# punch_driver_Rev_A.net
KiCad netlist of a schematic drawn in EAGLE
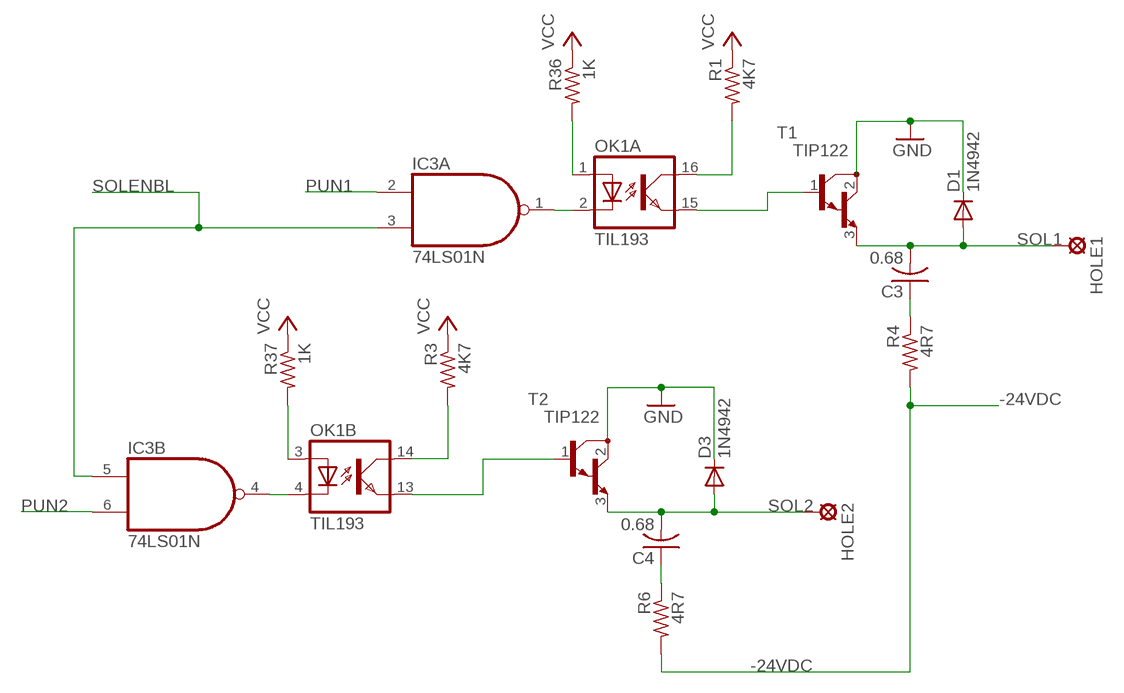
[diagram p0: schematic, sheet 1]
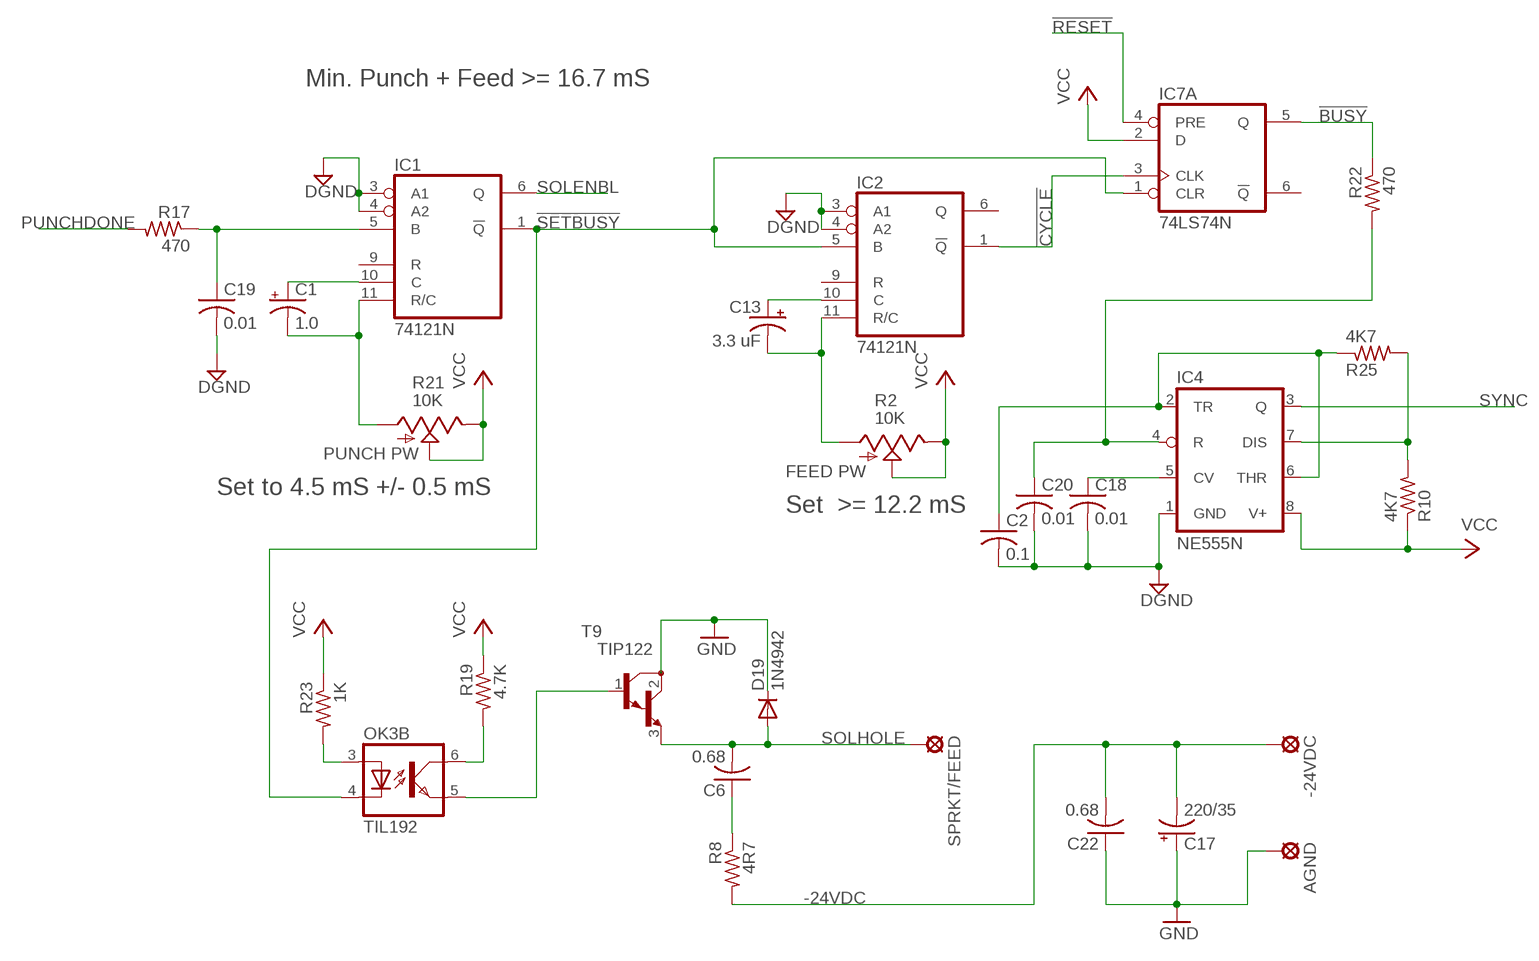
[diagram p1: schematic, sheet 2]
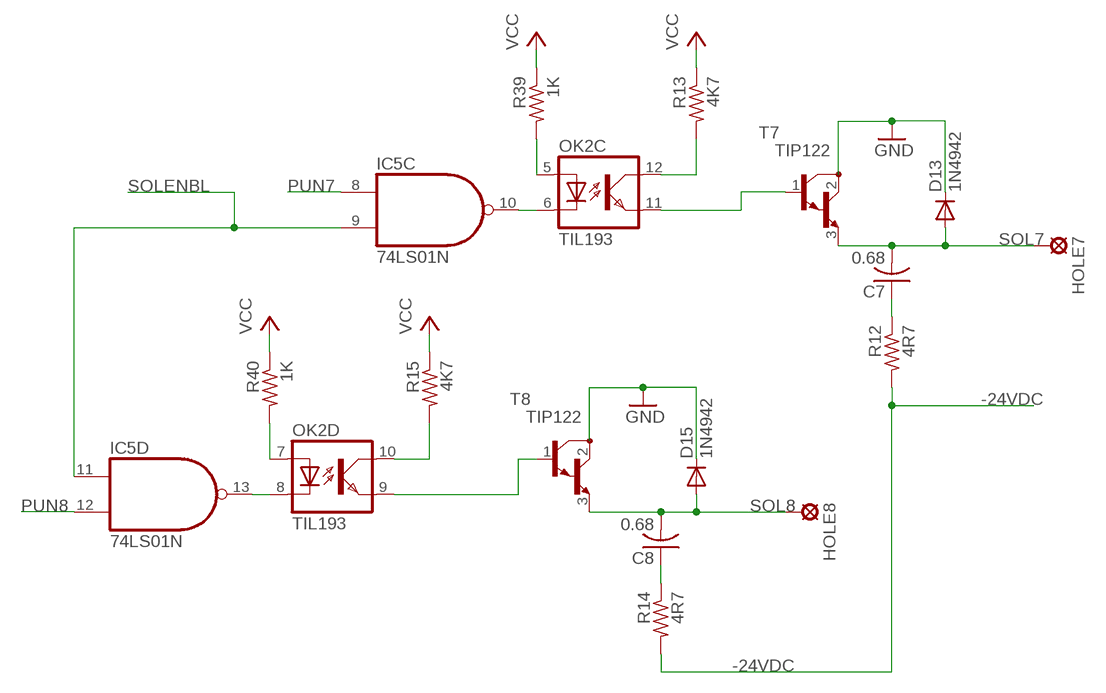
[diagram p2: schematic, sheet 3]
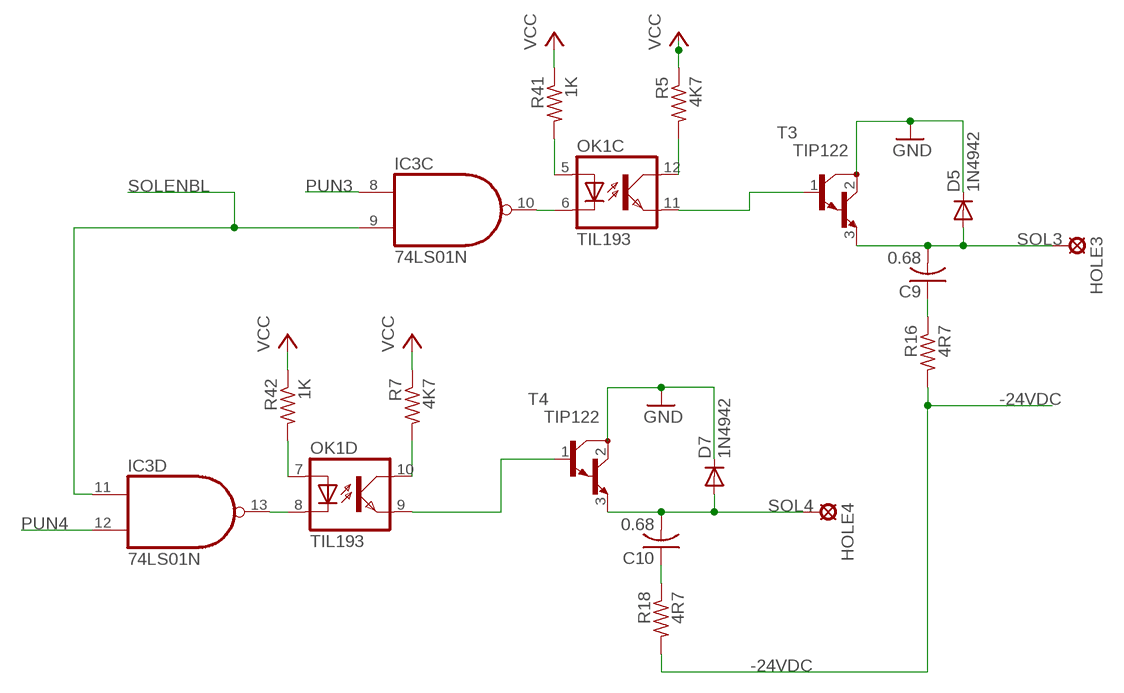
[diagram p3: schematic, sheet 4]
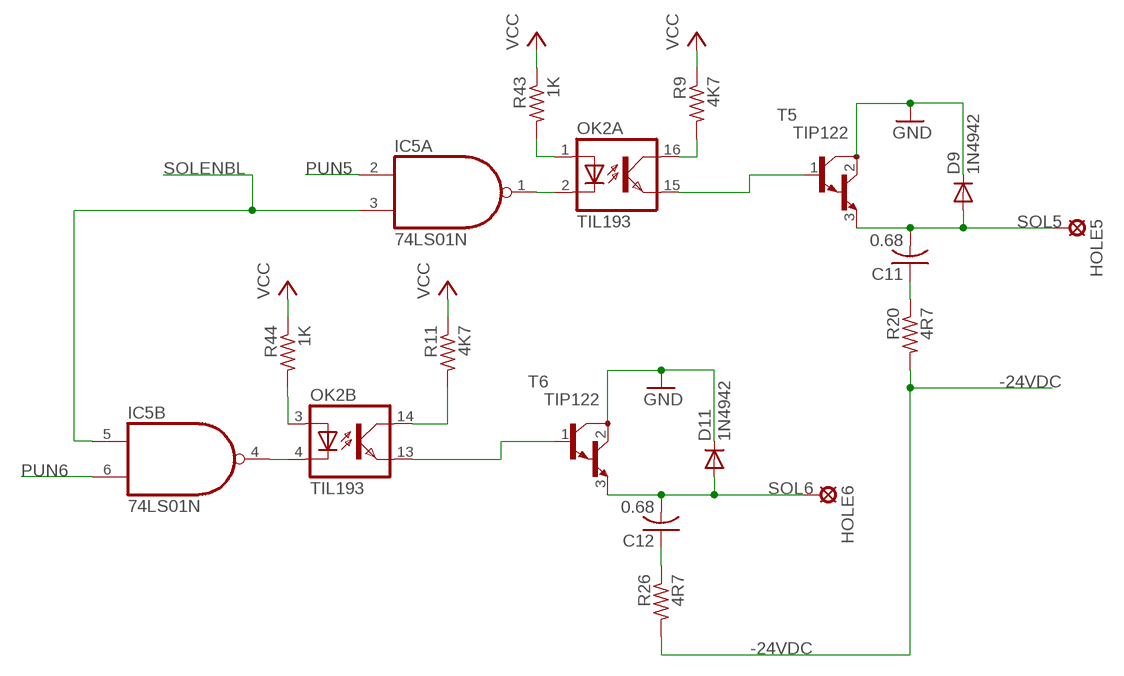
[diagram p4: schematic, sheet 5]
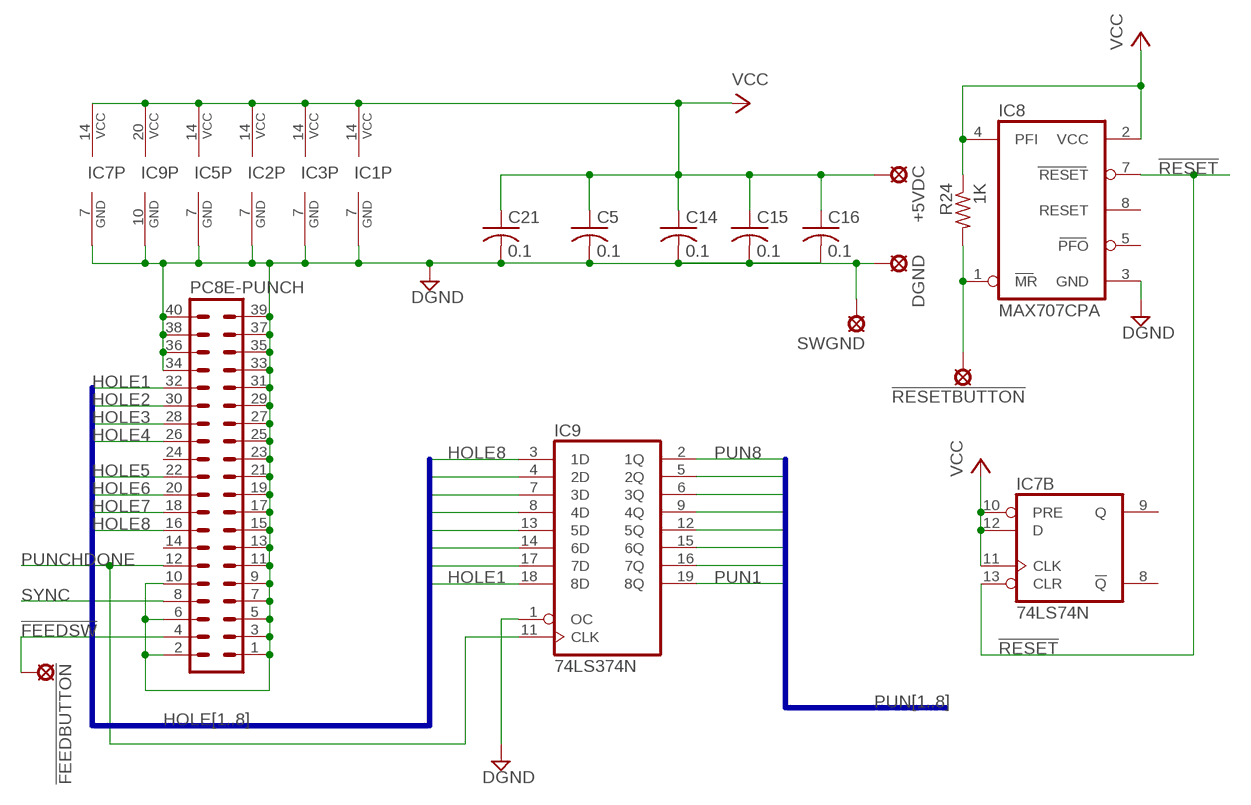
[diagram p5: schematic, sheet 6]

(export (version "E")
  (design (tool "Eeschema 10.0.6"))
  (components
    (comp (ref "C3")
      (value "0.68")
      (footprint "eagle-import:C075-042X103")
      (libsource (lib "eagle-import") (part "C-US075-042X103"))
    )
    (comp (ref "C4")
      (value "0.68")
      (footprint "eagle-import:C075-042X103")
      (libsource (lib "eagle-import") (part "C-US075-042X103"))
    )
    (comp (ref "D1")
      (value "1N4942")
      (footprint "eagle-import:DO41-10")
      (libsource (lib "eagle-import") (part "1N4942"))
    )
    (comp (ref "D3")
      (value "1N4942")
      (footprint "eagle-import:DO41-10")
      (libsource (lib "eagle-import") (part "1N4942"))
    )
    (comp (ref "HOLE1")
      (value "SE13")
      (footprint "eagle-import:SE13")
      (libsource (lib "eagle-import") (part "SE13"))
    )
    (comp (ref "HOLE2")
      (value "SE13")
      (footprint "eagle-import:SE13")
      (libsource (lib "eagle-import") (part "SE13"))
    )
    (comp (ref "IC3")
      (value "74LS01N")
      (footprint "eagle-import:DIL14")
      (libsource (lib "eagle-import") (part "7401NLS"))
    )
    (comp (ref "OK1")
      (value "TIL193")
      (footprint "eagle-import:DIL16")
      (libsource (lib "eagle-import") (part "TIL193"))
    )
    (comp (ref "R1")
      (value "4K7")
      (footprint "eagle-import:0204_5")
      (libsource (lib "eagle-import") (part "R-US_0204/5"))
    )
    (comp (ref "R3")
      (value "4K7")
      (footprint "eagle-import:0204_5")
      (libsource (lib "eagle-import") (part "R-US_0204/5"))
    )
    (comp (ref "R4")
      (value "4R7")
      (footprint "eagle-import:0207_10")
      (libsource (lib "eagle-import") (part "R-US_0207/10"))
    )
    (comp (ref "R6")
      (value "4R7")
      (footprint "eagle-import:0207_10")
      (libsource (lib "eagle-import") (part "R-US_0207/10"))
    )
    (comp (ref "R36")
      (value "1K")
      (footprint "eagle-import:0204_5")
      (libsource (lib "eagle-import") (part "R-US_0204/5"))
    )
    (comp (ref "R37")
      (value "1K")
      (footprint "eagle-import:0204_5")
      (libsource (lib "eagle-import") (part "R-US_0204/5"))
    )
    (comp (ref "T1")
      (value "TIP122")
      (footprint "eagle-import:TO220")
      (libsource (lib "eagle-import") (part "TIP122"))
    )
    (comp (ref "T2")
      (value "TIP122")
      (footprint "eagle-import:TO220")
      (libsource (lib "eagle-import") (part "TIP122"))
    )
    (comp (ref "C7")
      (value "0.68")
      (footprint "eagle-import:C075-042X103")
      (libsource (lib "eagle-import") (part "C-US075-042X103"))
    )
    (comp (ref "C8")
      (value "0.68")
      (footprint "eagle-import:C075-042X103")
      (libsource (lib "eagle-import") (part "C-US075-042X103"))
    )
    (comp (ref "D13")
      (value "1N4942")
      (footprint "eagle-import:DO41-10")
      (libsource (lib "eagle-import") (part "1N4942"))
    )
    (comp (ref "D15")
      (value "1N4942")
      (footprint "eagle-import:DO41-10")
      (libsource (lib "eagle-import") (part "1N4942"))
    )
    (comp (ref "HOLE7")
      (value "SE13")
      (footprint "eagle-import:SE13")
      (libsource (lib "eagle-import") (part "SE13"))
    )
    (comp (ref "HOLE8")
      (value "SE13")
      (footprint "eagle-import:SE13")
      (libsource (lib "eagle-import") (part "SE13"))
    )
    (comp (ref "IC5")
      (value "74LS01N")
      (footprint "eagle-import:DIL14")
      (libsource (lib "eagle-import") (part "7401NLS"))
    )
    (comp (ref "OK2")
      (value "TIL193")
      (footprint "eagle-import:DIL16")
      (libsource (lib "eagle-import") (part "TIL193"))
    )
    (comp (ref "R12")
      (value "4R7")
      (footprint "eagle-import:0207_10")
      (libsource (lib "eagle-import") (part "R-US_0207/10"))
    )
    (comp (ref "R13")
      (value "4K7")
      (footprint "eagle-import:0204_5")
      (libsource (lib "eagle-import") (part "R-US_0204/5"))
    )
    (comp (ref "R14")
      (value "4R7")
      (footprint "eagle-import:0207_10")
      (libsource (lib "eagle-import") (part "R-US_0207/10"))
    )
    (comp (ref "R15")
      (value "4K7")
      (footprint "eagle-import:0204_5")
      (libsource (lib "eagle-import") (part "R-US_0204/5"))
    )
    (comp (ref "R39")
      (value "1K")
      (footprint "eagle-import:0204_5")
      (libsource (lib "eagle-import") (part "R-US_0204/5"))
    )
    (comp (ref "R40")
      (value "1K")
      (footprint "eagle-import:0204_5")
      (libsource (lib "eagle-import") (part "R-US_0204/5"))
    )
    (comp (ref "T7")
      (value "TIP122")
      (footprint "eagle-import:TO220")
      (libsource (lib "eagle-import") (part "TIP122"))
    )
    (comp (ref "T8")
      (value "TIP122")
      (footprint "eagle-import:TO220")
      (libsource (lib "eagle-import") (part "TIP122"))
    )
    (comp (ref "-24VDC")
      (value "SE13")
      (footprint "eagle-import:SE13")
      (libsource (lib "eagle-import") (part "SE13"))
    )
    (comp (ref "AGND")
      (value "SE13")
      (footprint "eagle-import:SE13")
      (libsource (lib "eagle-import") (part "SE13"))
    )
    (comp (ref "C1")
      (value "1.0")
      (footprint "eagle-import:E5-10,5")
      (libsource (lib "eagle-import") (part "CPOL-USE5-10.5"))
    )
    (comp (ref "C2")
      (value "0.1")
      (footprint "eagle-import:C050-025X075")
      (libsource (lib "eagle-import") (part "C-US050-025X075"))
    )
    (comp (ref "C6")
      (value "0.68")
      (footprint "eagle-import:C075-042X103")
      (libsource (lib "eagle-import") (part "C-US075-042X103"))
    )
    (comp (ref "C13")
      (value "3.3 uF")
      (footprint "eagle-import:E5-10,5")
      (libsource (lib "eagle-import") (part "CPOL-USE5-10.5"))
    )
    (comp (ref "C17")
      (value "220/35")
      (footprint "eagle-import:E25-9")
      (libsource (lib "eagle-import") (part "CPOL-USE25-9AXIAL"))
    )
    (comp (ref "C18")
      (value "0.01")
      (footprint "eagle-import:C025-025X050")
      (libsource (lib "eagle-import") (part "C-US025-025X050"))
    )
    (comp (ref "C19")
      (value "0.01")
      (footprint "eagle-import:C025-025X050")
      (libsource (lib "eagle-import") (part "C-US025-025X050"))
    )
    (comp (ref "C20")
      (value "0.01")
      (footprint "eagle-import:C025-025X050")
      (libsource (lib "eagle-import") (part "C-US025-025X050"))
    )
    (comp (ref "C22")
      (value "0.68")
      (footprint "eagle-import:C075-042X103")
      (libsource (lib "eagle-import") (part "C-US075-042X103"))
    )
    (comp (ref "D19")
      (value "1N4942")
      (footprint "eagle-import:DO41-10")
      (libsource (lib "eagle-import") (part "1N4942"))
    )
    (comp (ref "IC1")
      (value "74121N")
      (footprint "eagle-import:DIL14")
      (libsource (lib "eagle-import") (part "74121N"))
    )
    (comp (ref "IC2")
      (value "74121N")
      (footprint "eagle-import:DIL14")
      (libsource (lib "eagle-import") (part "74121N"))
    )
    (comp (ref "IC4")
      (value "NE555N")
      (footprint "eagle-import:DIL08")
      (libsource (lib "eagle-import") (part "555NNE"))
    )
    (comp (ref "IC7")
      (value "74LS74N")
      (footprint "eagle-import:DIL14")
      (libsource (lib "eagle-import") (part "7474NLS"))
    )
    (comp (ref "OK3")
      (value "TIL192")
      (footprint "eagle-import:DIL08")
      (libsource (lib "eagle-import") (part "TIL192"))
    )
    (comp (ref "R2")
      (value "10K")
      (footprint "eagle-import:PT-SPIN")
      (libsource (lib "eagle-import") (part "TRIM_US-PTSPIN"))
    )
    (comp (ref "R8")
      (value "4R7")
      (footprint "eagle-import:0207_10")
      (libsource (lib "eagle-import") (part "R-US_0207/10"))
    )
    (comp (ref "R10")
      (value "4K7")
      (footprint "eagle-import:0204_5")
      (libsource (lib "eagle-import") (part "R-US_0204/5"))
    )
    (comp (ref "R17")
      (value "470")
      (footprint "eagle-import:0204_5")
      (libsource (lib "eagle-import") (part "R-US_0204/5"))
    )
    (comp (ref "R19")
      (value "4.7K")
      (footprint "eagle-import:0204_5")
      (libsource (lib "eagle-import") (part "R-US_0204/5"))
    )
    (comp (ref "R21")
      (value "10K")
      (footprint "eagle-import:PT-SPIN")
      (libsource (lib "eagle-import") (part "TRIM_US-PTSPIN"))
    )
    (comp (ref "R22")
      (value "470")
      (footprint "eagle-import:0204_5")
      (libsource (lib "eagle-import") (part "R-US_0204/5"))
    )
    (comp (ref "R23")
      (value "1K")
      (footprint "eagle-import:0204_5")
      (libsource (lib "eagle-import") (part "R-US_0204/5"))
    )
    (comp (ref "R25")
      (value "4K7")
      (footprint "eagle-import:0204_5")
      (libsource (lib "eagle-import") (part "R-US_0204/5"))
    )
    (comp (ref "SPRKT/FEED")
      (value "SE13")
      (footprint "eagle-import:SE13")
      (libsource (lib "eagle-import") (part "SE13"))
    )
    (comp (ref "T9")
      (value "TIP122")
      (footprint "eagle-import:TO220")
      (libsource (lib "eagle-import") (part "TIP122"))
    )
    (comp (ref "C9")
      (value "0.68")
      (footprint "eagle-import:C075-042X103")
      (libsource (lib "eagle-import") (part "C-US075-042X103"))
    )
    (comp (ref "C10")
      (value "0.68")
      (footprint "eagle-import:C075-042X103")
      (libsource (lib "eagle-import") (part "C-US075-042X103"))
    )
    (comp (ref "D5")
      (value "1N4942")
      (footprint "eagle-import:DO41-10")
      (libsource (lib "eagle-import") (part "1N4942"))
    )
    (comp (ref "D7")
      (value "1N4942")
      (footprint "eagle-import:DO41-10")
      (libsource (lib "eagle-import") (part "1N4942"))
    )
    (comp (ref "HOLE3")
      (value "SE13")
      (footprint "eagle-import:SE13")
      (libsource (lib "eagle-import") (part "SE13"))
    )
    (comp (ref "HOLE4")
      (value "SE13")
      (footprint "eagle-import:SE13")
      (libsource (lib "eagle-import") (part "SE13"))
    )
    (comp (ref "R5")
      (value "4K7")
      (footprint "eagle-import:0204_5")
      (libsource (lib "eagle-import") (part "R-US_0204/5"))
    )
    (comp (ref "R7")
      (value "4K7")
      (footprint "eagle-import:0204_5")
      (libsource (lib "eagle-import") (part "R-US_0204/5"))
    )
    (comp (ref "R16")
      (value "4R7")
      (footprint "eagle-import:0207_10")
      (libsource (lib "eagle-import") (part "R-US_0207/10"))
    )
    (comp (ref "R18")
      (value "4R7")
      (footprint "eagle-import:0207_10")
      (libsource (lib "eagle-import") (part "R-US_0207/10"))
    )
    (comp (ref "R41")
      (value "1K")
      (footprint "eagle-import:0204_5")
      (libsource (lib "eagle-import") (part "R-US_0204/5"))
    )
    (comp (ref "R42")
      (value "1K")
      (footprint "eagle-import:0204_5")
      (libsource (lib "eagle-import") (part "R-US_0204/5"))
    )
    (comp (ref "T3")
      (value "TIP122")
      (footprint "eagle-import:TO220")
      (libsource (lib "eagle-import") (part "TIP122"))
    )
    (comp (ref "T4")
      (value "TIP122")
      (footprint "eagle-import:TO220")
      (libsource (lib "eagle-import") (part "TIP122"))
    )
    (comp (ref "C11")
      (value "0.68")
      (footprint "eagle-import:C075-042X103")
      (libsource (lib "eagle-import") (part "C-US075-042X103"))
    )
    (comp (ref "C12")
      (value "0.68")
      (footprint "eagle-import:C075-042X103")
      (libsource (lib "eagle-import") (part "C-US075-042X103"))
    )
    (comp (ref "D9")
      (value "1N4942")
      (footprint "eagle-import:DO41-10")
      (libsource (lib "eagle-import") (part "1N4942"))
    )
    (comp (ref "D11")
      (value "1N4942")
      (footprint "eagle-import:DO41-10")
      (libsource (lib "eagle-import") (part "1N4942"))
    )
    (comp (ref "HOLE5")
      (value "SE13")
      (footprint "eagle-import:SE13")
      (libsource (lib "eagle-import") (part "SE13"))
    )
    (comp (ref "HOLE6")
      (value "SE13")
      (footprint "eagle-import:SE13")
      (libsource (lib "eagle-import") (part "SE13"))
    )
    (comp (ref "R9")
      (value "4K7")
      (footprint "eagle-import:0204_5")
      (libsource (lib "eagle-import") (part "R-US_0204/5"))
    )
    (comp (ref "R11")
      (value "4K7")
      (footprint "eagle-import:0204_5")
      (libsource (lib "eagle-import") (part "R-US_0204/5"))
    )
    (comp (ref "R20")
      (value "4R7")
      (footprint "eagle-import:0207_10")
      (libsource (lib "eagle-import") (part "R-US_0207/10"))
    )
    (comp (ref "R26")
      (value "4R7")
      (footprint "eagle-import:0207_10")
      (libsource (lib "eagle-import") (part "R-US_0207/10"))
    )
    (comp (ref "R43")
      (value "1K")
      (footprint "eagle-import:0204_5")
      (libsource (lib "eagle-import") (part "R-US_0204/5"))
    )
    (comp (ref "R44")
      (value "1K")
      (footprint "eagle-import:0204_5")
      (libsource (lib "eagle-import") (part "R-US_0204/5"))
    )
    (comp (ref "T5")
      (value "TIP122")
      (footprint "eagle-import:TO220")
      (libsource (lib "eagle-import") (part "TIP122"))
    )
    (comp (ref "T6")
      (value "TIP122")
      (footprint "eagle-import:TO220")
      (libsource (lib "eagle-import") (part "TIP122"))
    )
    (comp (ref "!FEEDBUTTON")
      (value "SE13")
      (footprint "eagle-import:SE13")
      (libsource (lib "eagle-import") (part "SE13"))
    )
    (comp (ref "!RESETBUTTON")
      (value "SE13")
      (footprint "eagle-import:SE13")
      (libsource (lib "eagle-import") (part "SE13"))
    )
    (comp (ref "+5VDC")
      (value "SE13")
      (footprint "eagle-import:SE13")
      (libsource (lib "eagle-import") (part "SE13"))
    )
    (comp (ref "C5")
      (value "0.1")
      (footprint "eagle-import:C050-025X075")
      (libsource (lib "eagle-import") (part "C-US050-025X075"))
    )
    (comp (ref "C14")
      (value "0.1")
      (footprint "eagle-import:C050-025X075")
      (libsource (lib "eagle-import") (part "C-US050-025X075"))
    )
    (comp (ref "C15")
      (value "0.1")
      (footprint "eagle-import:C050-025X075")
      (libsource (lib "eagle-import") (part "C-US050-025X075"))
    )
    (comp (ref "C16")
      (value "0.1")
      (footprint "eagle-import:C050-025X075")
      (libsource (lib "eagle-import") (part "C-US050-025X075"))
    )
    (comp (ref "C21")
      (value "0.1")
      (footprint "eagle-import:C050-025X075")
      (libsource (lib "eagle-import") (part "C-US050-025X075"))
    )
    (comp (ref "DGND")
      (value "SE13")
      (footprint "eagle-import:SE13")
      (libsource (lib "eagle-import") (part "SE13"))
    )
    (comp (ref "IC8")
      (value "MAX707CPA")
      (footprint "eagle-import:DIL08")
      (libsource (lib "eagle-import") (part "MAX707CPA"))
    )
    (comp (ref "IC9")
      (value "74LS374N")
      (footprint "eagle-import:DIL20")
      (libsource (lib "eagle-import") (part "74374NLS"))
    )
    (comp (ref "PC8E-PUNCH")
      (value "MA20-2")
      (footprint "eagle-import:MA20-2")
      (libsource (lib "eagle-import") (part "MA20-2"))
    )
    (comp (ref "R24")
      (value "1K")
      (footprint "eagle-import:0204_5")
      (libsource (lib "eagle-import") (part "R-US_0204/5"))
    )
    (comp (ref "SWGND")
      (value "SE13")
      (footprint "eagle-import:SE13")
      (libsource (lib "eagle-import") (part "SE13"))
    )
  )
  (nets
    (net (code "1") (name "-24VDC") (class "Default")
      (node (ref "-24VDC") (pin "MP") (pinfunction "MP_MP") (pintype "passive"))
      (node (ref "C17") (pin "-") (pinfunction "-_-") (pintype "passive"))
      (node (ref "C22") (pin "2") (pinfunction "2_2") (pintype "passive"))
      (node (ref "R12") (pin "2") (pinfunction "2_2") (pintype "passive"))
      (node (ref "R14") (pin "2") (pinfunction "2_2") (pintype "passive"))
      (node (ref "R16") (pin "2") (pinfunction "2_2") (pintype "passive"))
      (node (ref "R18") (pin "2") (pinfunction "2_2") (pintype "passive"))
      (node (ref "R20") (pin "2") (pinfunction "2_2") (pintype "passive"))
      (node (ref "R26") (pin "2") (pinfunction "2_2") (pintype "passive"))
      (node (ref "R4") (pin "2") (pinfunction "2_2") (pintype "passive"))
      (node (ref "R6") (pin "2") (pinfunction "2_2") (pintype "passive"))
      (node (ref "R8") (pin "2") (pinfunction "2_2") (pintype "passive"))
    )
    (net (code "4") (name "DGND") (class "Default")
      (node (ref "C14") (pin "2") (pinfunction "2_2") (pintype "passive"))
      (node (ref "C15") (pin "2") (pinfunction "2_2") (pintype "passive"))
      (node (ref "C16") (pin "2") (pinfunction "2_2") (pintype "passive"))
      (node (ref "C18") (pin "2") (pinfunction "2_2") (pintype "passive"))
      (node (ref "C19") (pin "2") (pinfunction "2_2") (pintype "passive"))
      (node (ref "C2") (pin "2") (pinfunction "2_2") (pintype "passive"))
      (node (ref "C20") (pin "2") (pinfunction "2_2") (pintype "passive"))
      (node (ref "C21") (pin "2") (pinfunction "2_2") (pintype "passive"))
      (node (ref "C5") (pin "2") (pinfunction "2_2") (pintype "passive"))
      (node (ref "DGND") (pin "MP") (pinfunction "MP_MP") (pintype "passive"))
      (node (ref "IC1") (pin "3") (pinfunction "A1_3") (pintype "input"))
      (node (ref "IC1") (pin "4") (pinfunction "A2_4") (pintype "input"))
      (node (ref "IC1") (pin "7") (pinfunction "GND_7") (pintype "power_in"))
      (node (ref "IC2") (pin "3") (pinfunction "A1_3") (pintype "input"))
      (node (ref "IC2") (pin "4") (pinfunction "A2_4") (pintype "input"))
      (node (ref "IC2") (pin "7") (pinfunction "GND_7") (pintype "power_in"))
      (node (ref "IC3") (pin "7") (pinfunction "GND_7") (pintype "power_in"))
      (node (ref "IC4") (pin "1") (pinfunction "GND_1") (pintype "power_in"))
      (node (ref "IC5") (pin "7") (pinfunction "GND_7") (pintype "power_in"))
      (node (ref "IC7") (pin "7") (pinfunction "GND_7") (pintype "power_in"))
      (node (ref "IC8") (pin "3") (pinfunction "GND_3") (pintype "power_in"))
      (node (ref "IC9") (pin "1") (pinfunction "OC_1") (pintype "input"))
      (node (ref "IC9") (pin "10") (pinfunction "GND_10") (pintype "power_in"))
      (node (ref "PC8E-PUNCH") (pin "1") (pinfunction "1_1") (pintype "passive"))
      (node (ref "PC8E-PUNCH") (pin "10") (pinfunction "10_10") (pintype "passive"))
      (node (ref "PC8E-PUNCH") (pin "11") (pinfunction "11_11") (pintype "passive"))
      (node (ref "PC8E-PUNCH") (pin "13") (pinfunction "13_13") (pintype "passive"))
      (node (ref "PC8E-PUNCH") (pin "15") (pinfunction "15_15") (pintype "passive"))
      (node (ref "PC8E-PUNCH") (pin "17") (pinfunction "17_17") (pintype "passive"))
      (node (ref "PC8E-PUNCH") (pin "19") (pinfunction "19_19") (pintype "passive"))
      (node (ref "PC8E-PUNCH") (pin "2") (pinfunction "2_2") (pintype "passive"))
      (node (ref "PC8E-PUNCH") (pin "21") (pinfunction "21_21") (pintype "passive"))
      (node (ref "PC8E-PUNCH") (pin "23") (pinfunction "23_23") (pintype "passive"))
      (node (ref "PC8E-PUNCH") (pin "25") (pinfunction "25_25") (pintype "passive"))
      (node (ref "PC8E-PUNCH") (pin "27") (pinfunction "27_27") (pintype "passive"))
      (node (ref "PC8E-PUNCH") (pin "29") (pinfunction "29_29") (pintype "passive"))
      (node (ref "PC8E-PUNCH") (pin "3") (pinfunction "3_3") (pintype "passive"))
      (node (ref "PC8E-PUNCH") (pin "31") (pinfunction "31_31") (pintype "passive"))
      (node (ref "PC8E-PUNCH") (pin "33") (pinfunction "33_33") (pintype "passive"))
      (node (ref "PC8E-PUNCH") (pin "34") (pinfunction "34_34") (pintype "passive"))
      (node (ref "PC8E-PUNCH") (pin "35") (pinfunction "35_35") (pintype "passive"))
      (node (ref "PC8E-PUNCH") (pin "36") (pinfunction "36_36") (pintype "passive"))
      (node (ref "PC8E-PUNCH") (pin "37") (pinfunction "37_37") (pintype "passive"))
      (node (ref "PC8E-PUNCH") (pin "38") (pinfunction "38_38") (pintype "passive"))
      (node (ref "PC8E-PUNCH") (pin "39") (pinfunction "39_39") (pintype "passive"))
      (node (ref "PC8E-PUNCH") (pin "40") (pinfunction "40_40") (pintype "passive"))
      (node (ref "PC8E-PUNCH") (pin "5") (pinfunction "5_5") (pintype "passive"))
      (node (ref "PC8E-PUNCH") (pin "6") (pinfunction "6_6") (pintype "passive"))
      (node (ref "PC8E-PUNCH") (pin "7") (pinfunction "7_7") (pintype "passive"))
      (node (ref "PC8E-PUNCH") (pin "9") (pinfunction "9_9") (pintype "passive"))
      (node (ref "SWGND") (pin "MP") (pinfunction "MP_MP") (pintype "passive"))
    )
    (net (code "5") (name "GND") (class "Default")
      (node (ref "AGND") (pin "MP") (pinfunction "MP_MP") (pintype "passive"))
      (node (ref "C17") (pin "+") (pinfunction "+_+") (pintype "passive"))
      (node (ref "C22") (pin "1") (pinfunction "1_1") (pintype "passive"))
      (node (ref "D1") (pin "C") (pinfunction "C_C") (pintype "passive"))
      (node (ref "D11") (pin "C") (pinfunction "C_C") (pintype "passive"))
      (node (ref "D13") (pin "C") (pinfunction "C_C") (pintype "passive"))
      (node (ref "D15") (pin "C") (pinfunction "C_C") (pintype "passive"))
      (node (ref "D19") (pin "C") (pinfunction "C_C") (pintype "passive"))
      (node (ref "D3") (pin "C") (pinfunction "C_C") (pintype "passive"))
      (node (ref "D5") (pin "C") (pinfunction "C_C") (pintype "passive"))
      (node (ref "D7") (pin "C") (pinfunction "C_C") (pintype "passive"))
      (node (ref "D9") (pin "C") (pinfunction "C_C") (pintype "passive"))
      (node (ref "T1") (pin "2") (pinfunction "C_2") (pintype "passive"))
      (node (ref "T2") (pin "2") (pinfunction "C_2") (pintype "passive"))
      (node (ref "T3") (pin "2") (pinfunction "C_2") (pintype "passive"))
      (node (ref "T4") (pin "2") (pinfunction "C_2") (pintype "passive"))
      (node (ref "T5") (pin "2") (pinfunction "C_2") (pintype "passive"))
      (node (ref "T6") (pin "2") (pinfunction "C_2") (pintype "passive"))
      (node (ref "T7") (pin "2") (pinfunction "C_2") (pintype "passive"))
      (node (ref "T8") (pin "2") (pinfunction "C_2") (pintype "passive"))
      (node (ref "T9") (pin "2") (pinfunction "C_2") (pintype "passive"))
    )
    (net (code "6") (name "HOLE1") (class "Default")
      (node (ref "IC9") (pin "18") (pinfunction "8D_18") (pintype "input"))
      (node (ref "PC8E-PUNCH") (pin "32") (pinfunction "32_32") (pintype "passive"))
    )
    (net (code "7") (name "HOLE2") (class "Default")
      (node (ref "IC9") (pin "17") (pinfunction "7D_17") (pintype "input"))
      (node (ref "PC8E-PUNCH") (pin "30") (pinfunction "30_30") (pintype "passive"))
    )
    (net (code "8") (name "HOLE3") (class "Default")
      (node (ref "IC9") (pin "14") (pinfunction "6D_14") (pintype "input"))
      (node (ref "PC8E-PUNCH") (pin "28") (pinfunction "28_28") (pintype "passive"))
    )
    (net (code "9") (name "HOLE4") (class "Default")
      (node (ref "IC9") (pin "13") (pinfunction "5D_13") (pintype "input"))
      (node (ref "PC8E-PUNCH") (pin "26") (pinfunction "26_26") (pintype "passive"))
    )
    (net (code "10") (name "HOLE5") (class "Default")
      (node (ref "IC9") (pin "8") (pinfunction "4D_8") (pintype "input"))
      (node (ref "PC8E-PUNCH") (pin "22") (pinfunction "22_22") (pintype "passive"))
    )
    (net (code "11") (name "HOLE6") (class "Default")
      (node (ref "IC9") (pin "7") (pinfunction "3D_7") (pintype "input"))
      (node (ref "PC8E-PUNCH") (pin "20") (pinfunction "20_20") (pintype "passive"))
    )
    (net (code "12") (name "HOLE7") (class "Default")
      (node (ref "IC9") (pin "4") (pinfunction "2D_4") (pintype "input"))
      (node (ref "PC8E-PUNCH") (pin "18") (pinfunction "18_18") (pintype "passive"))
    )
    (net (code "13") (name "HOLE8") (class "Default")
      (node (ref "IC9") (pin "3") (pinfunction "1D_3") (pintype "input"))
      (node (ref "PC8E-PUNCH") (pin "16") (pinfunction "16_16") (pintype "passive"))
    )
    (net (code "14") (name "Net-(C3-Pad1)") (class "Default")
      (node (ref "C3") (pin "1") (pinfunction "1_1") (pintype "passive"))
      (node (ref "R4") (pin "1") (pinfunction "1_1") (pintype "passive"))
    )
    (net (code "15") (name "Net-(C4-Pad1)") (class "Default")
      (node (ref "C4") (pin "1") (pinfunction "1_1") (pintype "passive"))
      (node (ref "R6") (pin "1") (pinfunction "1_1") (pintype "passive"))
    )
    (net (code "16") (name "Net-(C6-Pad1)") (class "Default")
      (node (ref "C6") (pin "1") (pinfunction "1_1") (pintype "passive"))
      (node (ref "R8") (pin "1") (pinfunction "1_1") (pintype "passive"))
    )
    (net (code "17") (name "Net-(C7-Pad1)") (class "Default")
      (node (ref "C7") (pin "1") (pinfunction "1_1") (pintype "passive"))
      (node (ref "R12") (pin "1") (pinfunction "1_1") (pintype "passive"))
    )
    (net (code "18") (name "Net-(C8-Pad1)") (class "Default")
      (node (ref "C8") (pin "1") (pinfunction "1_1") (pintype "passive"))
      (node (ref "R14") (pin "1") (pinfunction "1_1") (pintype "passive"))
    )
    (net (code "19") (name "Net-(C9-Pad1)") (class "Default")
      (node (ref "C9") (pin "1") (pinfunction "1_1") (pintype "passive"))
      (node (ref "R16") (pin "1") (pinfunction "1_1") (pintype "passive"))
    )
    (net (code "20") (name "Net-(C10-Pad1)") (class "Default")
      (node (ref "C10") (pin "1") (pinfunction "1_1") (pintype "passive"))
      (node (ref "R18") (pin "1") (pinfunction "1_1") (pintype "passive"))
    )
    (net (code "21") (name "Net-(C11-Pad1)") (class "Default")
      (node (ref "C11") (pin "1") (pinfunction "1_1") (pintype "passive"))
      (node (ref "R20") (pin "1") (pinfunction "1_1") (pintype "passive"))
    )
    (net (code "22") (name "Net-(C12-Pad1)") (class "Default")
      (node (ref "C12") (pin "1") (pinfunction "1_1") (pintype "passive"))
      (node (ref "R26") (pin "1") (pinfunction "1_1") (pintype "passive"))
    )
    (net (code "23") (name "Net-(IC1A-B)") (class "Default")
      (node (ref "C19") (pin "1") (pinfunction "1_1") (pintype "passive"))
      (node (ref "IC1") (pin "5") (pinfunction "B_5") (pintype "input"))
      (node (ref "R17") (pin "1") (pinfunction "1_1") (pintype "passive"))
    )
    (net (code "24") (name "Net-(IC1A-C)") (class "Default")
      (node (ref "C1") (pin "+") (pinfunction "+_+") (pintype "passive"))
      (node (ref "IC1") (pin "10") (pinfunction "C_10") (pintype "input"))
    )
    (net (code "25") (name "Net-(IC1A-R{slash}C)") (class "Default")
      (node (ref "C1") (pin "-") (pinfunction "-_-") (pintype "passive"))
      (node (ref "IC1") (pin "11") (pinfunction "R/C_11") (pintype "input"))
      (node (ref "R21") (pin "A") (pinfunction "A_A") (pintype "passive"))
    )
    (net (code "26") (name "Net-(IC2A-C)") (class "Default")
      (node (ref "C13") (pin "+") (pinfunction "+_+") (pintype "passive"))
      (node (ref "IC2") (pin "10") (pinfunction "C_10") (pintype "input"))
    )
    (net (code "27") (name "Net-(IC2A-R{slash}C)") (class "Default")
      (node (ref "C13") (pin "-") (pinfunction "-_-") (pintype "passive"))
      (node (ref "IC2") (pin "11") (pinfunction "R/C_11") (pintype "input"))
      (node (ref "R2") (pin "A") (pinfunction "A_A") (pintype "passive"))
    )
    (net (code "28") (name "Net-(IC3A-O)") (class "Default")
      (node (ref "IC3") (pin "1") (pinfunction "O_1") (pintype "open_collector"))
      (node (ref "OK1") (pin "2") (pinfunction "C_2") (pintype "passive"))
    )
    (net (code "29") (name "Net-(IC3B-O)") (class "Default")
      (node (ref "IC3") (pin "4") (pinfunction "O_4") (pintype "open_collector"))
      (node (ref "OK1") (pin "4") (pinfunction "C_4") (pintype "passive"))
    )
    (net (code "30") (name "Net-(IC3C-O)") (class "Default")
      (node (ref "IC3") (pin "10") (pinfunction "O_10") (pintype "open_collector"))
      (node (ref "OK1") (pin "6") (pinfunction "C_6") (pintype "passive"))
    )
    (net (code "31") (name "Net-(IC3D-O)") (class "Default")
      (node (ref "IC3") (pin "13") (pinfunction "O_13") (pintype "open_collector"))
      (node (ref "OK1") (pin "8") (pinfunction "C_8") (pintype "passive"))
    )
    (net (code "32") (name "Net-(IC4-CV)") (class "Default")
      (node (ref "C18") (pin "1") (pinfunction "1_1") (pintype "passive"))
      (node (ref "IC4") (pin "5") (pinfunction "CV_5") (pintype "input"))
    )
    (net (code "33") (name "Net-(IC4-DIS)") (class "Default")
      (node (ref "IC4") (pin "7") (pinfunction "DIS_7") (pintype "input"))
      (node (ref "R10") (pin "2") (pinfunction "2_2") (pintype "passive"))
      (node (ref "R25") (pin "2") (pinfunction "2_2") (pintype "passive"))
    )
    (net (code "34") (name "Net-(IC4-R)") (class "Default")
      (node (ref "C20") (pin "1") (pinfunction "1_1") (pintype "passive"))
      (node (ref "IC4") (pin "4") (pinfunction "R_4") (pintype "input"))
      (node (ref "R22") (pin "2") (pinfunction "2_2") (pintype "passive"))
    )
    (net (code "35") (name "Net-(IC4-THR)") (class "Default")
      (node (ref "C2") (pin "1") (pinfunction "1_1") (pintype "passive"))
      (node (ref "IC4") (pin "2") (pinfunction "TR_2") (pintype "input"))
      (node (ref "IC4") (pin "6") (pinfunction "THR_6") (pintype "input"))
      (node (ref "R25") (pin "1") (pinfunction "1_1") (pintype "passive"))
    )
    (net (code "36") (name "Net-(IC5A-O)") (class "Default")
      (node (ref "IC5") (pin "1") (pinfunction "O_1") (pintype "open_collector"))
      (node (ref "OK2") (pin "2") (pinfunction "C_2") (pintype "passive"))
    )
    (net (code "37") (name "Net-(IC5B-O)") (class "Default")
      (node (ref "IC5") (pin "4") (pinfunction "O_4") (pintype "open_collector"))
      (node (ref "OK2") (pin "4") (pinfunction "C_4") (pintype "passive"))
    )
    (net (code "38") (name "Net-(IC5C-O)") (class "Default")
      (node (ref "IC5") (pin "10") (pinfunction "O_10") (pintype "open_collector"))
      (node (ref "OK2") (pin "6") (pinfunction "C_6") (pintype "passive"))
    )
    (net (code "39") (name "Net-(IC5D-O)") (class "Default")
      (node (ref "IC5") (pin "13") (pinfunction "O_13") (pintype "open_collector"))
      (node (ref "OK2") (pin "8") (pinfunction "C_8") (pintype "passive"))
    )
    (net (code "40") (name "Net-(IC8-MR)") (class "Default")
      (node (ref "!RESETBUTTON") (pin "MP") (pinfunction "MP_MP") (pintype "passive"))
      (node (ref "IC8") (pin "1") (pinfunction "MR_1") (pintype "input"))
      (node (ref "R24") (pin "2") (pinfunction "2_2") (pintype "passive"))
    )
    (net (code "41") (name "Net-(OK1A-A)") (class "Default")
      (node (ref "OK1") (pin "1") (pinfunction "A_1") (pintype "passive"))
      (node (ref "R36") (pin "2") (pinfunction "2_2") (pintype "passive"))
    )
    (net (code "42") (name "Net-(OK1A-COL)") (class "Default")
      (node (ref "OK1") (pin "16") (pinfunction "COL_16") (pintype "passive"))
      (node (ref "R1") (pin "2") (pinfunction "2_2") (pintype "passive"))
    )
    (net (code "43") (name "Net-(OK1A-EMIT)") (class "Default")
      (node (ref "OK1") (pin "15") (pinfunction "EMIT_15") (pintype "passive"))
      (node (ref "T1") (pin "1") (pinfunction "B_1") (pintype "passive"))
    )
    (net (code "44") (name "Net-(OK1B-A)") (class "Default")
      (node (ref "OK1") (pin "3") (pinfunction "A_3") (pintype "passive"))
      (node (ref "R37") (pin "2") (pinfunction "2_2") (pintype "passive"))
    )
    (net (code "45") (name "Net-(OK1B-COL)") (class "Default")
      (node (ref "OK1") (pin "14") (pinfunction "COL_14") (pintype "passive"))
      (node (ref "R3") (pin "2") (pinfunction "2_2") (pintype "passive"))
    )
    (net (code "46") (name "Net-(OK1B-EMIT)") (class "Default")
      (node (ref "OK1") (pin "13") (pinfunction "EMIT_13") (pintype "passive"))
      (node (ref "T2") (pin "1") (pinfunction "B_1") (pintype "passive"))
    )
    (net (code "47") (name "Net-(OK1C-A)") (class "Default")
      (node (ref "OK1") (pin "5") (pinfunction "A_5") (pintype "passive"))
      (node (ref "R41") (pin "2") (pinfunction "2_2") (pintype "passive"))
    )
    (net (code "48") (name "Net-(OK1C-COL)") (class "Default")
      (node (ref "OK1") (pin "12") (pinfunction "COL_12") (pintype "passive"))
      (node (ref "R5") (pin "2") (pinfunction "2_2") (pintype "passive"))
    )
    (net (code "49") (name "Net-(OK1C-EMIT)") (class "Default")
      (node (ref "OK1") (pin "11") (pinfunction "EMIT_11") (pintype "passive"))
      (node (ref "T3") (pin "1") (pinfunction "B_1") (pintype "passive"))
    )
    (net (code "50") (name "Net-(OK1D-A)") (class "Default")
      (node (ref "OK1") (pin "7") (pinfunction "A_7") (pintype "passive"))
      (node (ref "R42") (pin "2") (pinfunction "2_2") (pintype "passive"))
    )
    (net (code "51") (name "Net-(OK1D-COL)") (class "Default")
      (node (ref "OK1") (pin "10") (pinfunction "COL_10") (pintype "passive"))
      (node (ref "R7") (pin "2") (pinfunction "2_2") (pintype "passive"))
    )
    (net (code "52") (name "Net-(OK1D-EMIT)") (class "Default")
      (node (ref "OK1") (pin "9") (pinfunction "EMIT_9") (pintype "passive"))
      (node (ref "T4") (pin "1") (pinfunction "B_1") (pintype "passive"))
    )
    (net (code "53") (name "Net-(OK2A-A)") (class "Default")
      (node (ref "OK2") (pin "1") (pinfunction "A_1") (pintype "passive"))
      (node (ref "R43") (pin "2") (pinfunction "2_2") (pintype "passive"))
    )
    (net (code "54") (name "Net-(OK2A-COL)") (class "Default")
      (node (ref "OK2") (pin "16") (pinfunction "COL_16") (pintype "passive"))
      (node (ref "R9") (pin "2") (pinfunction "2_2") (pintype "passive"))
    )
    (net (code "55") (name "Net-(OK2A-EMIT)") (class "Default")
      (node (ref "OK2") (pin "15") (pinfunction "EMIT_15") (pintype "passive"))
      (node (ref "T5") (pin "1") (pinfunction "B_1") (pintype "passive"))
    )
    (net (code "56") (name "Net-(OK2B-A)") (class "Default")
      (node (ref "OK2") (pin "3") (pinfunction "A_3") (pintype "passive"))
      (node (ref "R44") (pin "2") (pinfunction "2_2") (pintype "passive"))
    )
    (net (code "57") (name "Net-(OK2B-COL)") (class "Default")
      (node (ref "OK2") (pin "14") (pinfunction "COL_14") (pintype "passive"))
      (node (ref "R11") (pin "2") (pinfunction "2_2") (pintype "passive"))
    )
    (net (code "58") (name "Net-(OK2B-EMIT)") (class "Default")
      (node (ref "OK2") (pin "13") (pinfunction "EMIT_13") (pintype "passive"))
      (node (ref "T6") (pin "1") (pinfunction "B_1") (pintype "passive"))
    )
    (net (code "59") (name "Net-(OK2C-A)") (class "Default")
      (node (ref "OK2") (pin "5") (pinfunction "A_5") (pintype "passive"))
      (node (ref "R39") (pin "2") (pinfunction "2_2") (pintype "passive"))
    )
    (net (code "60") (name "Net-(OK2C-COL)") (class "Default")
      (node (ref "OK2") (pin "12") (pinfunction "COL_12") (pintype "passive"))
      (node (ref "R13") (pin "2") (pinfunction "2_2") (pintype "passive"))
    )
    (net (code "61") (name "Net-(OK2C-EMIT)") (class "Default")
      (node (ref "OK2") (pin "11") (pinfunction "EMIT_11") (pintype "passive"))
      (node (ref "T7") (pin "1") (pinfunction "B_1") (pintype "passive"))
    )
    (net (code "62") (name "Net-(OK2D-A)") (class "Default")
      (node (ref "OK2") (pin "7") (pinfunction "A_7") (pintype "passive"))
      (node (ref "R40") (pin "2") (pinfunction "2_2") (pintype "passive"))
    )
    (net (code "63") (name "Net-(OK2D-COL)") (class "Default")
      (node (ref "OK2") (pin "10") (pinfunction "COL_10") (pintype "passive"))
      (node (ref "R15") (pin "2") (pinfunction "2_2") (pintype "passive"))
    )
    (net (code "64") (name "Net-(OK2D-EMIT)") (class "Default")
      (node (ref "OK2") (pin "9") (pinfunction "EMIT_9") (pintype "passive"))
      (node (ref "T8") (pin "1") (pinfunction "B_1") (pintype "passive"))
    )
    (net (code "65") (name "Net-(OK3B-A)") (class "Default")
      (node (ref "OK3") (pin "3") (pinfunction "A_3") (pintype "passive"))
      (node (ref "R23") (pin "2") (pinfunction "2_2") (pintype "passive"))
    )
    (net (code "66") (name "Net-(OK3B-COL)") (class "Default")
      (node (ref "OK3") (pin "6") (pinfunction "COL_6") (pintype "passive"))
      (node (ref "R19") (pin "2") (pinfunction "2_2") (pintype "passive"))
    )
    (net (code "67") (name "Net-(OK3B-EMIT)") (class "Default")
      (node (ref "OK3") (pin "5") (pinfunction "EMIT_5") (pintype "passive"))
      (node (ref "T9") (pin "1") (pinfunction "B_1") (pintype "passive"))
    )
    (net (code "68") (name "PUN1") (class "Default")
      (node (ref "IC3") (pin "2") (pinfunction "I0_2") (pintype "input"))
      (node (ref "IC9") (pin "19") (pinfunction "8Q_19") (pintype "tri_state"))
    )
    (net (code "69") (name "PUN2") (class "Default")
      (node (ref "IC3") (pin "6") (pinfunction "I1_6") (pintype "input"))
      (node (ref "IC9") (pin "16") (pinfunction "7Q_16") (pintype "tri_state"))
    )
    (net (code "70") (name "PUN3") (class "Default")
      (node (ref "IC3") (pin "8") (pinfunction "I0_8") (pintype "input"))
      (node (ref "IC9") (pin "15") (pinfunction "6Q_15") (pintype "tri_state"))
    )
    (net (code "71") (name "PUN4") (class "Default")
      (node (ref "IC3") (pin "12") (pinfunction "I1_12") (pintype "input"))
      (node (ref "IC9") (pin "12") (pinfunction "5Q_12") (pintype "tri_state"))
    )
    (net (code "72") (name "PUN5") (class "Default")
      (node (ref "IC5") (pin "2") (pinfunction "I0_2") (pintype "input"))
      (node (ref "IC9") (pin "9") (pinfunction "4Q_9") (pintype "tri_state"))
    )
    (net (code "73") (name "PUN6") (class "Default")
      (node (ref "IC5") (pin "6") (pinfunction "I1_6") (pintype "input"))
      (node (ref "IC9") (pin "6") (pinfunction "3Q_6") (pintype "tri_state"))
    )
    (net (code "74") (name "PUN7") (class "Default")
      (node (ref "IC5") (pin "8") (pinfunction "I0_8") (pintype "input"))
      (node (ref "IC9") (pin "5") (pinfunction "2Q_5") (pintype "tri_state"))
    )
    (net (code "75") (name "PUN8") (class "Default")
      (node (ref "IC5") (pin "12") (pinfunction "I1_12") (pintype "input"))
      (node (ref "IC9") (pin "2") (pinfunction "1Q_2") (pintype "tri_state"))
    )
    (net (code "76") (name "PUNCHDONE") (class "Default")
      (node (ref "IC9") (pin "11") (pinfunction "CLK_11") (pintype "input"))
      (node (ref "PC8E-PUNCH") (pin "12") (pinfunction "12_12") (pintype "passive"))
      (node (ref "R17") (pin "2") (pinfunction "2_2") (pintype "passive"))
    )
    (net (code "77") (name "SOL1") (class "Default")
      (node (ref "C3") (pin "2") (pinfunction "2_2") (pintype "passive"))
      (node (ref "D1") (pin "A") (pinfunction "A_A") (pintype "passive"))
      (node (ref "HOLE1") (pin "MP") (pinfunction "MP_MP") (pintype "passive"))
      (node (ref "T1") (pin "3") (pinfunction "E_3") (pintype "passive"))
    )
    (net (code "78") (name "SOL2") (class "Default")
      (node (ref "C4") (pin "2") (pinfunction "2_2") (pintype "passive"))
      (node (ref "D3") (pin "A") (pinfunction "A_A") (pintype "passive"))
      (node (ref "HOLE2") (pin "MP") (pinfunction "MP_MP") (pintype "passive"))
      (node (ref "T2") (pin "3") (pinfunction "E_3") (pintype "passive"))
    )
    (net (code "79") (name "SOL3") (class "Default")
      (node (ref "C9") (pin "2") (pinfunction "2_2") (pintype "passive"))
      (node (ref "D5") (pin "A") (pinfunction "A_A") (pintype "passive"))
      (node (ref "HOLE3") (pin "MP") (pinfunction "MP_MP") (pintype "passive"))
      (node (ref "T3") (pin "3") (pinfunction "E_3") (pintype "passive"))
    )
    (net (code "80") (name "SOL4") (class "Default")
      (node (ref "C10") (pin "2") (pinfunction "2_2") (pintype "passive"))
      (node (ref "D7") (pin "A") (pinfunction "A_A") (pintype "passive"))
      (node (ref "HOLE4") (pin "MP") (pinfunction "MP_MP") (pintype "passive"))
      (node (ref "T4") (pin "3") (pinfunction "E_3") (pintype "passive"))
    )
    (net (code "81") (name "SOL5") (class "Default")
      (node (ref "C11") (pin "2") (pinfunction "2_2") (pintype "passive"))
      (node (ref "D9") (pin "A") (pinfunction "A_A") (pintype "passive"))
      (node (ref "HOLE5") (pin "MP") (pinfunction "MP_MP") (pintype "passive"))
      (node (ref "T5") (pin "3") (pinfunction "E_3") (pintype "passive"))
    )
    (net (code "82") (name "SOL6") (class "Default")
      (node (ref "C12") (pin "2") (pinfunction "2_2") (pintype "passive"))
      (node (ref "D11") (pin "A") (pinfunction "A_A") (pintype "passive"))
      (node (ref "HOLE6") (pin "MP") (pinfunction "MP_MP") (pintype "passive"))
      (node (ref "T6") (pin "3") (pinfunction "E_3") (pintype "passive"))
    )
    (net (code "83") (name "SOL7") (class "Default")
      (node (ref "C7") (pin "2") (pinfunction "2_2") (pintype "passive"))
      (node (ref "D13") (pin "A") (pinfunction "A_A") (pintype "passive"))
      (node (ref "HOLE7") (pin "MP") (pinfunction "MP_MP") (pintype "passive"))
      (node (ref "T7") (pin "3") (pinfunction "E_3") (pintype "passive"))
    )
    (net (code "84") (name "SOL8") (class "Default")
      (node (ref "C8") (pin "2") (pinfunction "2_2") (pintype "passive"))
      (node (ref "D15") (pin "A") (pinfunction "A_A") (pintype "passive"))
      (node (ref "HOLE8") (pin "MP") (pinfunction "MP_MP") (pintype "passive"))
      (node (ref "T8") (pin "3") (pinfunction "E_3") (pintype "passive"))
    )
    (net (code "85") (name "SOLENBL") (class "Default")
      (node (ref "IC1") (pin "6") (pinfunction "Q_6") (pintype "output"))
      (node (ref "IC3") (pin "11") (pinfunction "I0_11") (pintype "input"))
      (node (ref "IC3") (pin "3") (pinfunction "I1_3") (pintype "input"))
      (node (ref "IC3") (pin "5") (pinfunction "I0_5") (pintype "input"))
      (node (ref "IC3") (pin "9") (pinfunction "I1_9") (pintype "input"))
      (node (ref "IC5") (pin "11") (pinfunction "I0_11") (pintype "input"))
      (node (ref "IC5") (pin "3") (pinfunction "I1_3") (pintype "input"))
      (node (ref "IC5") (pin "5") (pinfunction "I0_5") (pintype "input"))
      (node (ref "IC5") (pin "9") (pinfunction "I1_9") (pintype "input"))
    )
    (net (code "86") (name "SOLHOLE") (class "Default")
      (node (ref "C6") (pin "2") (pinfunction "2_2") (pintype "passive"))
      (node (ref "D19") (pin "A") (pinfunction "A_A") (pintype "passive"))
      (node (ref "SPRKT/FEED") (pin "MP") (pinfunction "MP_MP") (pintype "passive"))
      (node (ref "T9") (pin "3") (pinfunction "E_3") (pintype "passive"))
    )
    (net (code "87") (name "SYNC") (class "Default")
      (node (ref "IC4") (pin "3") (pinfunction "Q_3") (pintype "output"))
      (node (ref "PC8E-PUNCH") (pin "8") (pinfunction "8_8") (pintype "passive"))
    )
    (net (code "88") (name "VCC") (class "Default")
      (node (ref "+5VDC") (pin "MP") (pinfunction "MP_MP") (pintype "passive"))
      (node (ref "C14") (pin "1") (pinfunction "1_1") (pintype "passive"))
      (node (ref "C15") (pin "1") (pinfunction "1_1") (pintype "passive"))
      (node (ref "C16") (pin "1") (pinfunction "1_1") (pintype "passive"))
      (node (ref "C21") (pin "1") (pinfunction "1_1") (pintype "passive"))
      (node (ref "C5") (pin "1") (pinfunction "1_1") (pintype "passive"))
      (node (ref "IC1") (pin "14") (pinfunction "VCC_14") (pintype "power_in"))
      (node (ref "IC2") (pin "14") (pinfunction "VCC_14") (pintype "power_in"))
      (node (ref "IC3") (pin "14") (pinfunction "VCC_14") (pintype "power_in"))
      (node (ref "IC4") (pin "8") (pinfunction "V+_8") (pintype "power_in"))
      (node (ref "IC5") (pin "14") (pinfunction "VCC_14") (pintype "power_in"))
      (node (ref "IC7") (pin "10") (pinfunction "PRE_10") (pintype "input"))
      (node (ref "IC7") (pin "11") (pinfunction "CLK_11") (pintype "input"))
      (node (ref "IC7") (pin "12") (pinfunction "D_12") (pintype "input"))
      (node (ref "IC7") (pin "14") (pinfunction "VCC_14") (pintype "power_in"))
      (node (ref "IC7") (pin "2") (pinfunction "D_2") (pintype "input"))
      (node (ref "IC8") (pin "2") (pinfunction "VCC_2") (pintype "power_in"))
      (node (ref "IC8") (pin "4") (pinfunction "PFI_4") (pintype "input"))
      (node (ref "IC9") (pin "20") (pinfunction "VCC_20") (pintype "power_in"))
      (node (ref "R1") (pin "1") (pinfunction "1_1") (pintype "passive"))
      (node (ref "R10") (pin "1") (pinfunction "1_1") (pintype "passive"))
      (node (ref "R11") (pin "1") (pinfunction "1_1") (pintype "passive"))
      (node (ref "R13") (pin "1") (pinfunction "1_1") (pintype "passive"))
      (node (ref "R15") (pin "1") (pinfunction "1_1") (pintype "passive"))
      (node (ref "R19") (pin "1") (pinfunction "1_1") (pintype "passive"))
      (node (ref "R2") (pin "E") (pinfunction "E_E") (pintype "passive"))
      (node (ref "R2") (pin "S") (pinfunction "S_S") (pintype "passive"))
      (node (ref "R21") (pin "E") (pinfunction "E_E") (pintype "passive"))
      (node (ref "R21") (pin "S") (pinfunction "S_S") (pintype "passive"))
      (node (ref "R23") (pin "1") (pinfunction "1_1") (pintype "passive"))
      (node (ref "R24") (pin "1") (pinfunction "1_1") (pintype "passive"))
      (node (ref "R3") (pin "1") (pinfunction "1_1") (pintype "passive"))
      (node (ref "R36") (pin "1") (pinfunction "1_1") (pintype "passive"))
      (node (ref "R37") (pin "1") (pinfunction "1_1") (pintype "passive"))
      (node (ref "R39") (pin "1") (pinfunction "1_1") (pintype "passive"))
      (node (ref "R40") (pin "1") (pinfunction "1_1") (pintype "passive"))
      (node (ref "R41") (pin "1") (pinfunction "1_1") (pintype "passive"))
      (node (ref "R42") (pin "1") (pinfunction "1_1") (pintype "passive"))
      (node (ref "R43") (pin "1") (pinfunction "1_1") (pintype "passive"))
      (node (ref "R44") (pin "1") (pinfunction "1_1") (pintype "passive"))
      (node (ref "R5") (pin "1") (pinfunction "1_1") (pintype "passive"))
      (node (ref "R7") (pin "1") (pinfunction "1_1") (pintype "passive"))
      (node (ref "R9") (pin "1") (pinfunction "1_1") (pintype "passive"))
    )
    (net (code "89") (name "unconnected-(IC1A-R-Pad9)") (class "Default")
      (node (ref "IC1") (pin "9") (pinfunction "R_9") (pintype "input"))
    )
    (net (code "90") (name "unconnected-(IC2A-Q-Pad6)") (class "Default")
      (node (ref "IC2") (pin "6") (pinfunction "Q_6") (pintype "output"))
    )
    (net (code "91") (name "unconnected-(IC2A-R-Pad9)") (class "Default")
      (node (ref "IC2") (pin "9") (pinfunction "R_9") (pintype "input"))
    )
    (net (code "92") (name "unconnected-(IC7A-~{Q}-Pad6)") (class "Default")
      (node (ref "IC7") (pin "6") (pinfunction "~{Q}_6") (pintype "output"))
    )
    (net (code "93") (name "unconnected-(IC7B-Q-Pad9)") (class "Default")
      (node (ref "IC7") (pin "9") (pinfunction "Q_9") (pintype "output"))
    )
    (net (code "94") (name "unconnected-(IC7B-~{Q}-Pad8)") (class "Default")
      (node (ref "IC7") (pin "8") (pinfunction "~{Q}_8") (pintype "output"))
    )
    (net (code "95") (name "unconnected-(IC8-PFO-Pad5)") (class "Default")
      (node (ref "IC8") (pin "5") (pinfunction "PFO_5") (pintype "output"))
    )
    (net (code "96") (name "unconnected-(IC8-RESET-Pad8)") (class "Default")
      (node (ref "IC8") (pin "8") (pinfunction "RESET_8") (pintype "output"))
    )
    (net (code "97") (name "unconnected-(PC8E-PUNCH-Pad14)") (class "Default")
      (node (ref "PC8E-PUNCH") (pin "14") (pinfunction "14_14") (pintype "passive"))
    )
    (net (code "98") (name "unconnected-(PC8E-PUNCH-Pad24)") (class "Default")
      (node (ref "PC8E-PUNCH") (pin "24") (pinfunction "24_24") (pintype "passive"))
    )
    (net (code "99") (name "~{BUSY}") (class "Default")
      (node (ref "IC7") (pin "5") (pinfunction "Q_5") (pintype "output"))
      (node (ref "R22") (pin "1") (pinfunction "1_1") (pintype "passive"))
    )
    (net (code "100") (name "~{CYCLE}") (class "Default")
      (node (ref "IC2") (pin "1") (pinfunction "~{Q}_1") (pintype "output"))
      (node (ref "IC7") (pin "3") (pinfunction "CLK_3") (pintype "input"))
    )
    (net (code "101") (name "~{FEEDSW}") (class "Default")
      (node (ref "!FEEDBUTTON") (pin "MP") (pinfunction "MP_MP") (pintype "passive"))
      (node (ref "PC8E-PUNCH") (pin "4") (pinfunction "4_4") (pintype "passive"))
    )
    (net (code "102") (name "~{RESET}") (class "Default")
      (node (ref "IC7") (pin "13") (pinfunction "CLR_13") (pintype "input"))
      (node (ref "IC7") (pin "4") (pinfunction "PRE_4") (pintype "input"))
      (node (ref "IC8") (pin "7") (pinfunction "RESET_7") (pintype "output"))
    )
    (net (code "103") (name "~{SETBUSY}") (class "Default")
      (node (ref "IC1") (pin "1") (pinfunction "~{Q}_1") (pintype "output"))
      (node (ref "IC2") (pin "5") (pinfunction "B_5") (pintype "input"))
      (node (ref "IC7") (pin "1") (pinfunction "CLR_1") (pintype "input"))
      (node (ref "OK3") (pin "4") (pinfunction "C_4") (pintype "passive"))
    )
  )
)
